# SCH_NFC-Card-Martim_2024-10-10.net
KiCad netlist of a schematic drawn in EasyEDA
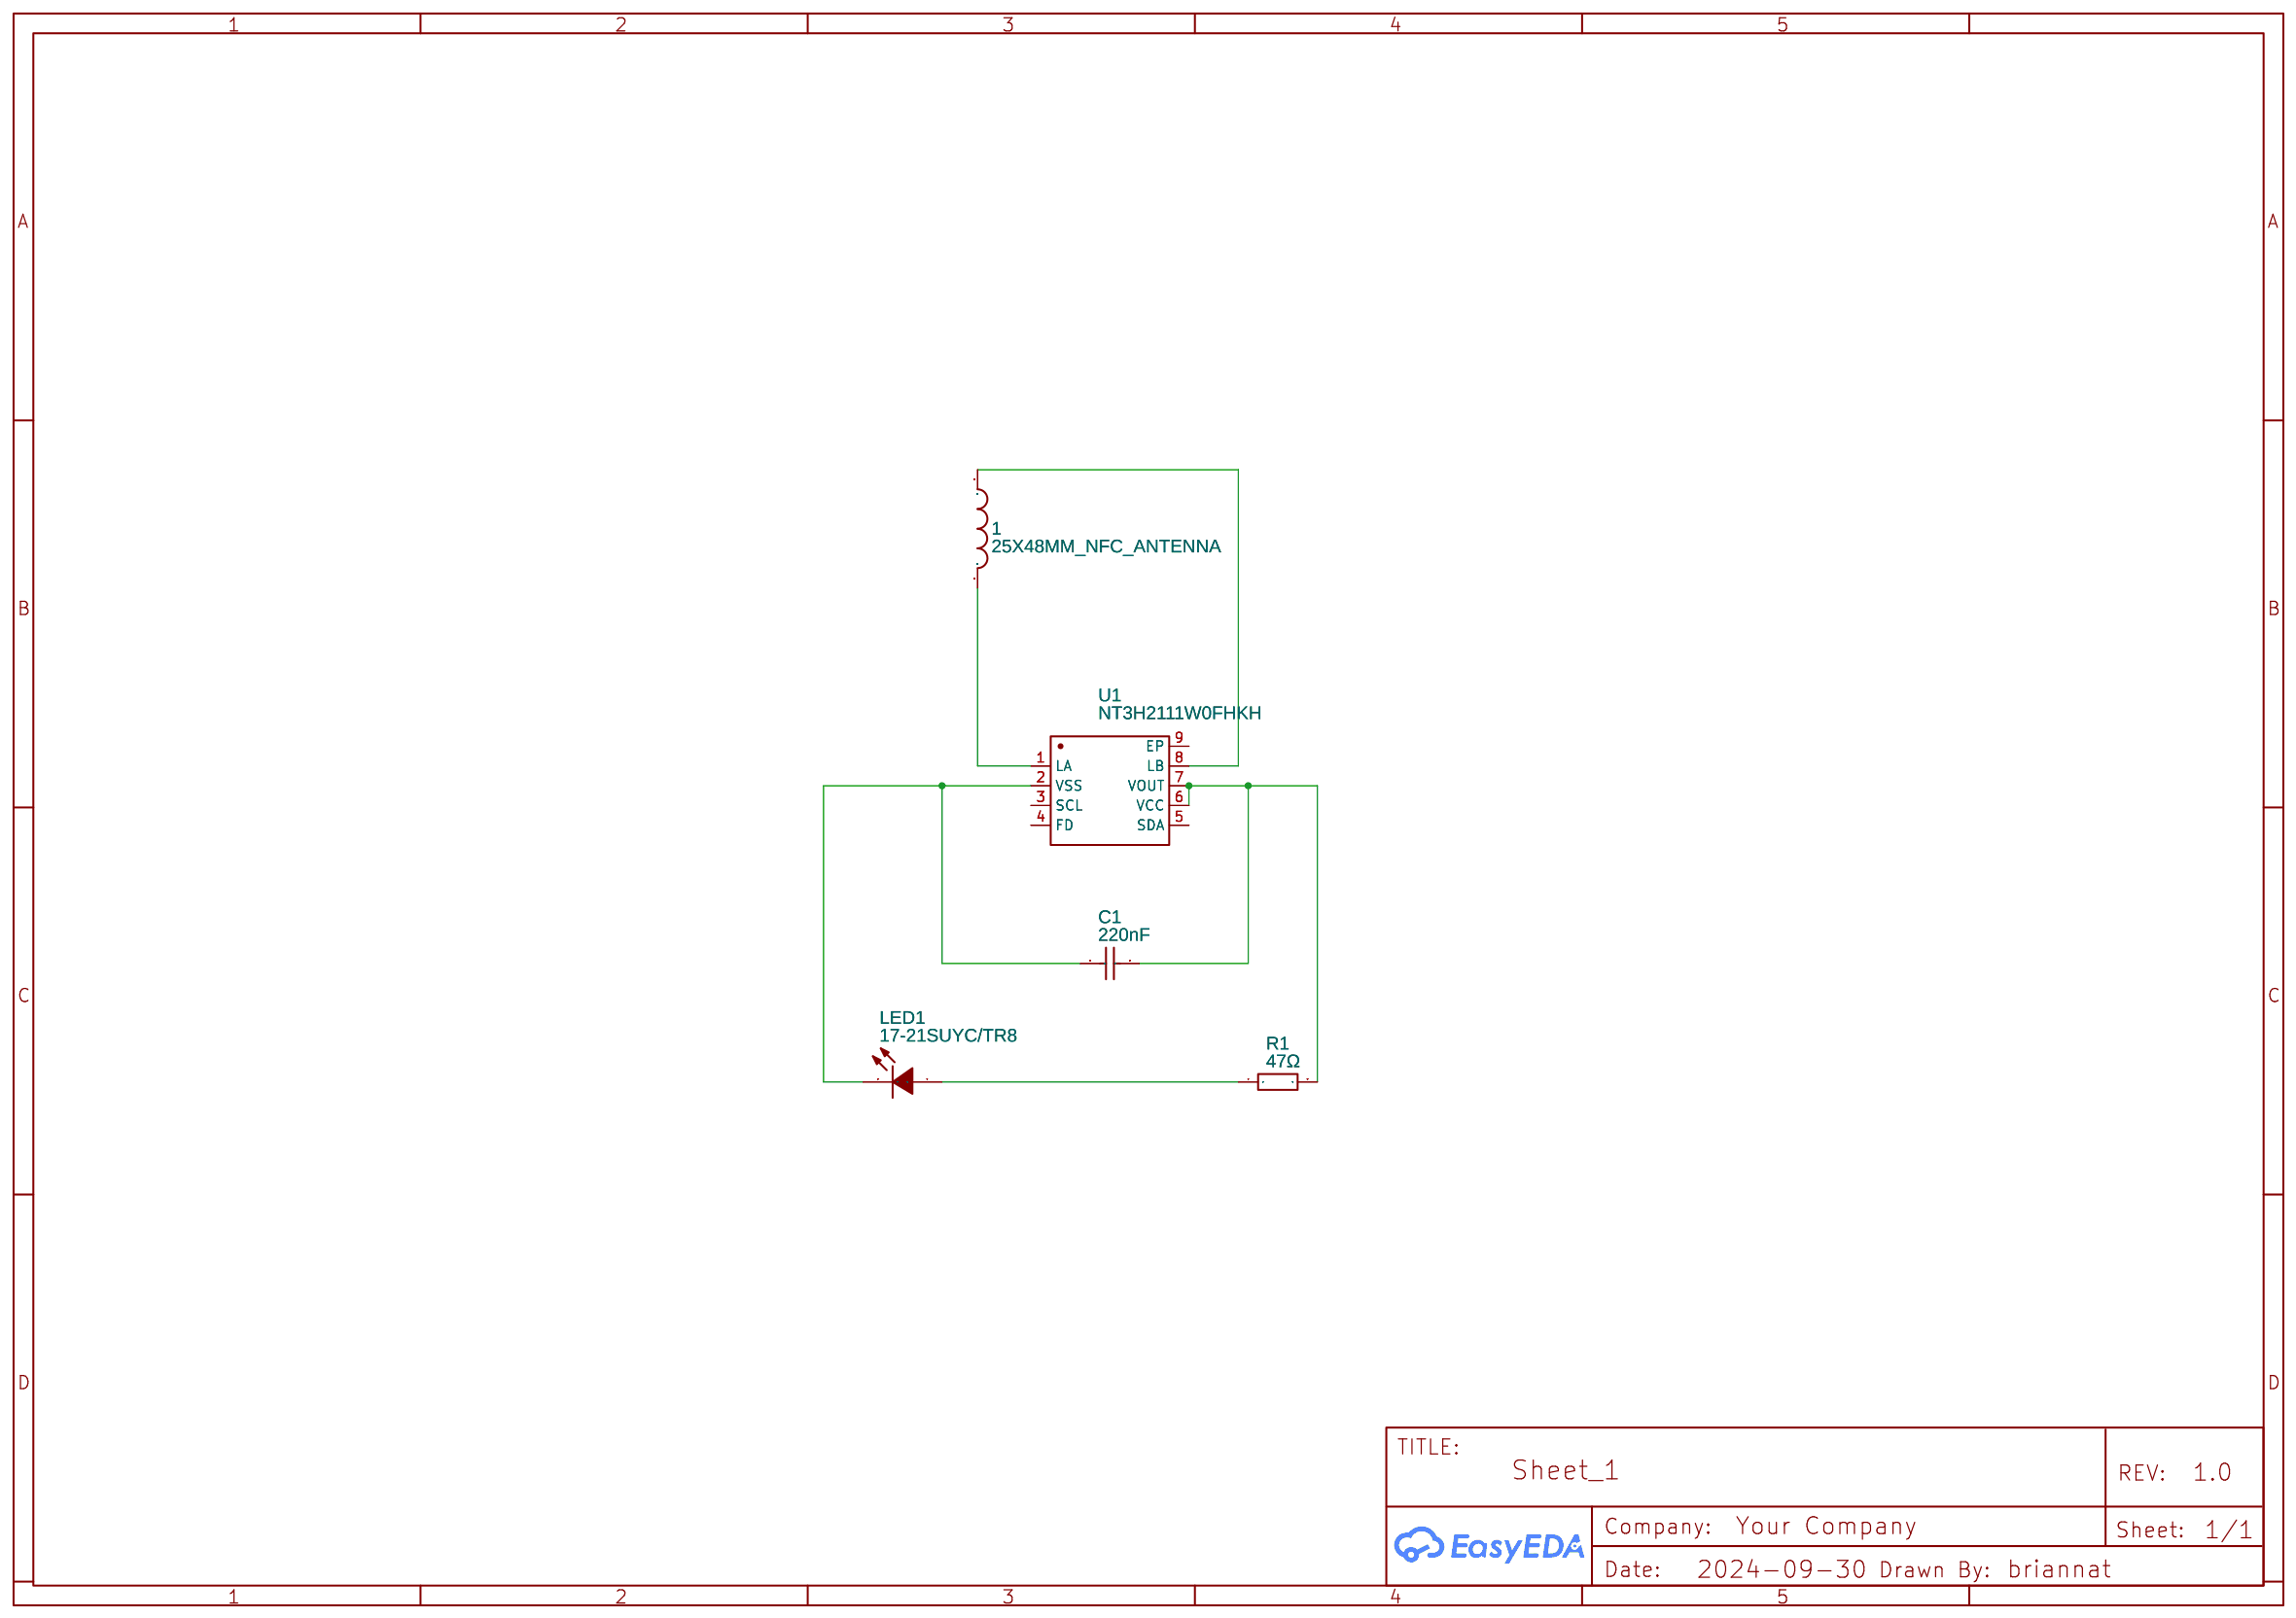
[diagram p0: schematic sheet]

(export (version "E")
  (design (tool "Eeschema 10.0.6"))
  (components
    (comp (ref "1") (value "25X48MM_NFC_ANTENNA") (libsource (lib "") (part "25X48MM_NFC_ANTENNA")))
    (comp (ref "C1")
      (value "220nF")
      (fields
        (field (name "Manufacturer Part") "CL10B224KA8NNNC")
        (field (name "Manufacturer") "SAMSUNG(三星)")
      )
      (libsource (lib "") (part "CL10B224KA8NNNC"))
    )
    (comp (ref "LED1")
      (value "17-21SUYC/TR8")
      (fields (field (name "Manufacturer Part") "KT-0805黄灯") (field (name "Manufacturer") "KENTO"))
      (libsource (lib "") (part "17-21SUYC/TR8"))
    )
    (comp (ref "R1")
      (value "47Ω")
      (fields
        (field (name "Manufacturer Part") "0603WAF470JT5E")
        (field (name "Manufacturer") "UNI-ROYAL(厚声)")
      )
      (libsource (lib "") (part "0603WAF470JT5E"))
    )
    (comp (ref "U1")
      (value "NT3H2111W0FHKH")
      (fields (field (name "Manufacturer") "NXP(恩智浦)"))
      (libsource (lib "") (part "NT3H2111W0FHKH"))
    )
  )
  (nets
    (net (code "1") (name "Net-(LED1-+)") (class "Default")
      (node (ref "LED1") (pin "1") (pinfunction "+_1") (pintype "unspecified"))
      (node (ref "R1") (pin "1") (pinfunction "1_1") (pintype "input"))
    )
    (net (code "2") (name "Net-(LED1--)") (class "Default")
      (node (ref "C1") (pin "1") (pinfunction "1_1") (pintype "input"))
      (node (ref "LED1") (pin "2") (pinfunction "-_2") (pintype "unspecified"))
      (node (ref "U1") (pin "2") (pinfunction "VSS_2") (pintype "unspecified"))
    )
    (net (code "3") (name "Net-(U1-LA)") (class "Default")
      (node (ref "1") (pin "P$2") (pinfunction "P$2_P$2") (pintype "bidirectional"))
      (node (ref "U1") (pin "1") (pinfunction "LA_1") (pintype "unspecified"))
    )
    (net (code "4") (name "Net-(U1-LB)") (class "Default")
      (node (ref "1") (pin "P$1") (pinfunction "P$1_P$1") (pintype "bidirectional"))
      (node (ref "U1") (pin "8") (pinfunction "LB_8") (pintype "unspecified"))
    )
    (net (code "5") (name "Net-(U1-VCC)") (class "Default")
      (node (ref "C1") (pin "2") (pinfunction "2_2") (pintype "input"))
      (node (ref "R1") (pin "2") (pinfunction "2_2") (pintype "input"))
      (node (ref "U1") (pin "6") (pinfunction "VCC_6") (pintype "unspecified"))
      (node (ref "U1") (pin "7") (pinfunction "VOUT_7") (pintype "unspecified"))
    )
    (net (code "6") (name "unconnected-(U1-EP-Pad9)") (class "Default")
      (node (ref "U1") (pin "9") (pinfunction "EP_9") (pintype "unspecified"))
    )
    (net (code "7") (name "unconnected-(U1-FD-Pad4)") (class "Default")
      (node (ref "U1") (pin "4") (pinfunction "FD_4") (pintype "unspecified"))
    )
    (net (code "8") (name "unconnected-(U1-SCL-Pad3)") (class "Default")
      (node (ref "U1") (pin "3") (pinfunction "SCL_3") (pintype "unspecified"))
    )
    (net (code "9") (name "unconnected-(U1-SDA-Pad5)") (class "Default")
      (node (ref "U1") (pin "5") (pinfunction "SDA_5") (pintype "unspecified"))
    )
  )
)
